# K210_Board.net
KiCad netlist of a schematic drawn in Altium Designer
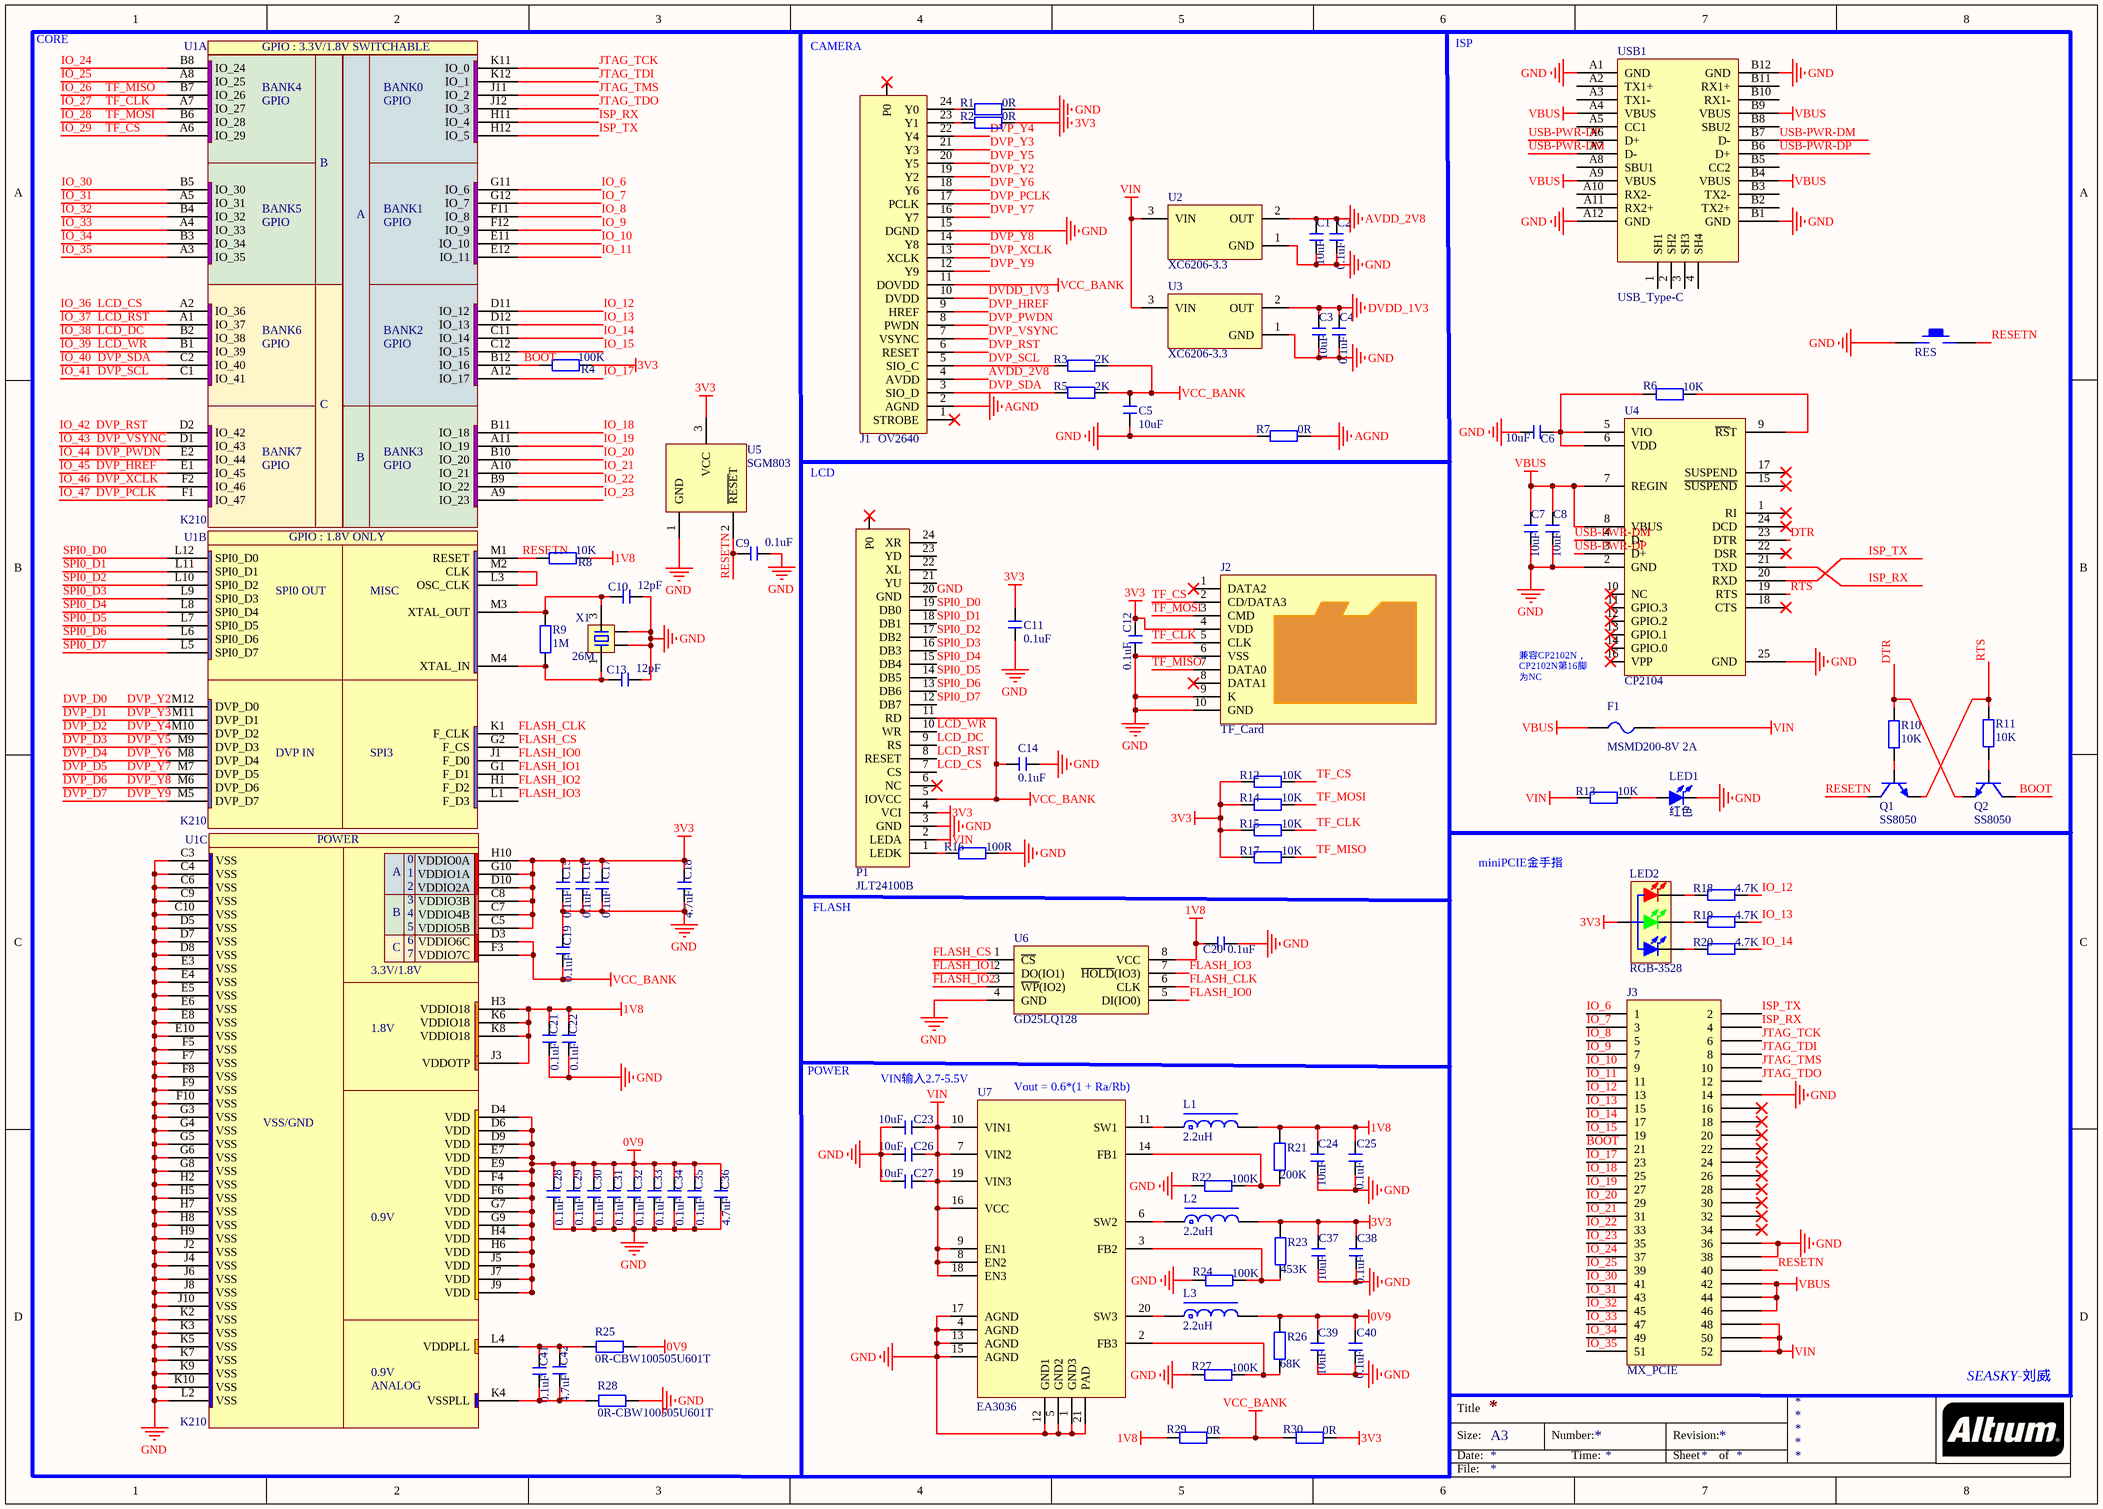
[diagram p0: K210_Board.SchDoc]

(export (version "E")
  (design (tool "Eeschema 10.0.6"))
  (components
    (comp (ref "C1")
      (value "10uF")
      (footprint "C 0402_M")
      (description "贴片电容")
      (libsource (lib "0.1 - 电阻-电容-电感") (part "C"))
    )
    (comp (ref "C2")
      (value "0.1uF")
      (footprint "C 0402_M")
      (description "贴片电容")
      (libsource (lib "0.1 - 电阻-电容-电感") (part "C"))
    )
    (comp (ref "C3")
      (value "10uF")
      (footprint "C 0402_M")
      (description "贴片电容")
      (libsource (lib "0.1 - 电阻-电容-电感") (part "C"))
    )
    (comp (ref "C4")
      (value "0.1uF")
      (footprint "C 0402_M")
      (description "贴片电容")
      (libsource (lib "0.1 - 电阻-电容-电感") (part "C"))
    )
    (comp (ref "C5")
      (value "10uF")
      (footprint "C 0402_M")
      (description "贴片电容")
      (libsource (lib "0.1 - 电阻-电容-电感") (part "C"))
    )
    (comp (ref "C6")
      (value "10uF")
      (footprint "C 0402_M")
      (description "贴片电容")
      (libsource (lib "0.1 - 电阻-电容-电感") (part "C"))
    )
    (comp (ref "C7")
      (value "10uF")
      (footprint "C 0402_M")
      (description "贴片电容")
      (libsource (lib "0.1 - 电阻-电容-电感") (part "C"))
    )
    (comp (ref "C8")
      (value "10uF")
      (footprint "C 0402_M")
      (description "贴片电容")
      (libsource (lib "0.1 - 电阻-电容-电感") (part "C"))
    )
    (comp (ref "C9")
      (value "0.1uF")
      (footprint "C 0402_M")
      (description "贴片电容")
      (libsource (lib "0.1 - 电阻-电容-电感") (part "C"))
    )
    (comp (ref "C10")
      (value "12pF")
      (footprint "C 0402_M")
      (description "贴片电容")
      (libsource (lib "0.1 - 电阻-电容-电感") (part "C"))
    )
    (comp (ref "C11")
      (value "0.1uF")
      (footprint "C 0402_M")
      (description "贴片电容")
      (libsource (lib "0.1 - 电阻-电容-电感") (part "C"))
    )
    (comp (ref "C12")
      (value "0.1uF")
      (footprint "C 0402_M")
      (description "贴片电容")
      (libsource (lib "0.1 - 电阻-电容-电感") (part "C"))
    )
    (comp (ref "C13")
      (value "12pF")
      (footprint "C 0402_M")
      (description "贴片电容")
      (libsource (lib "0.1 - 电阻-电容-电感") (part "C"))
    )
    (comp (ref "C14")
      (value "0.1uF")
      (footprint "C 0402_M")
      (description "贴片电容")
      (libsource (lib "0.1 - 电阻-电容-电感") (part "C"))
    )
    (comp (ref "C15")
      (value "0.1uF")
      (footprint "C 0402_M")
      (description "贴片电容")
      (libsource (lib "0.1 - 电阻-电容-电感") (part "C"))
    )
    (comp (ref "C16")
      (value "0.1uF")
      (footprint "C 0402_M")
      (description "贴片电容")
      (libsource (lib "0.1 - 电阻-电容-电感") (part "C"))
    )
    (comp (ref "C17")
      (value "0.1uF")
      (footprint "C 0402_M")
      (description "贴片电容")
      (libsource (lib "0.1 - 电阻-电容-电感") (part "C"))
    )
    (comp (ref "C18")
      (value "4.7uF")
      (footprint "C 0402_M")
      (description "贴片电容")
      (libsource (lib "0.1 - 电阻-电容-电感") (part "C"))
    )
    (comp (ref "C19")
      (value "0.1uF")
      (footprint "C 0402_M")
      (description "贴片电容")
      (libsource (lib "0.1 - 电阻-电容-电感") (part "C"))
    )
    (comp (ref "C20")
      (value "0.1uF")
      (footprint "C 0402_M")
      (description "贴片电容")
      (libsource (lib "0.1 - 电阻-电容-电感") (part "C"))
    )
    (comp (ref "C21")
      (value "0.1uF")
      (footprint "C 0402_M")
      (description "贴片电容")
      (libsource (lib "0.1 - 电阻-电容-电感") (part "C"))
    )
    (comp (ref "C22")
      (value "0.1uF")
      (footprint "C 0402_M")
      (description "贴片电容")
      (libsource (lib "0.1 - 电阻-电容-电感") (part "C"))
    )
    (comp (ref "C23")
      (value "10uF")
      (footprint "C 0402_M")
      (description "贴片电容")
      (libsource (lib "0.1 - 电阻-电容-电感") (part "C"))
    )
    (comp (ref "C24")
      (value "10uF")
      (footprint "C 0402_M")
      (description "贴片电容")
      (libsource (lib "0.1 - 电阻-电容-电感") (part "C"))
    )
    (comp (ref "C25")
      (value "0.1uF")
      (footprint "C 0402_M")
      (description "贴片电容")
      (libsource (lib "0.1 - 电阻-电容-电感") (part "C"))
    )
    (comp (ref "C26")
      (value "10uF")
      (footprint "C 0402_M")
      (description "贴片电容")
      (libsource (lib "0.1 - 电阻-电容-电感") (part "C"))
    )
    (comp (ref "C27")
      (value "10uF")
      (footprint "C 0402_M")
      (description "贴片电容")
      (libsource (lib "0.1 - 电阻-电容-电感") (part "C"))
    )
    (comp (ref "C28")
      (value "0.1uF")
      (footprint "C 0402_M")
      (description "贴片电容")
      (libsource (lib "0.1 - 电阻-电容-电感") (part "C"))
    )
    (comp (ref "C29")
      (value "0.1uF")
      (footprint "C 0402_M")
      (description "贴片电容")
      (libsource (lib "0.1 - 电阻-电容-电感") (part "C"))
    )
    (comp (ref "C30")
      (value "0.1uF")
      (footprint "C 0402_M")
      (description "贴片电容")
      (libsource (lib "0.1 - 电阻-电容-电感") (part "C"))
    )
    (comp (ref "C31")
      (value "0.1uF")
      (footprint "C 0402_M")
      (description "贴片电容")
      (libsource (lib "0.1 - 电阻-电容-电感") (part "C"))
    )
    (comp (ref "C32")
      (value "0.1uF")
      (footprint "C 0402_M")
      (description "贴片电容")
      (libsource (lib "0.1 - 电阻-电容-电感") (part "C"))
    )
    (comp (ref "C33")
      (value "0.1uF")
      (footprint "C 0402_M")
      (description "贴片电容")
      (libsource (lib "0.1 - 电阻-电容-电感") (part "C"))
    )
    (comp (ref "C34")
      (value "0.1uF")
      (footprint "C 0402_M")
      (description "贴片电容")
      (libsource (lib "0.1 - 电阻-电容-电感") (part "C"))
    )
    (comp (ref "C35")
      (value "0.1uF")
      (footprint "C 0402_M")
      (description "贴片电容")
      (libsource (lib "0.1 - 电阻-电容-电感") (part "C"))
    )
    (comp (ref "C36")
      (value "4.7uF")
      (footprint "C 0402_M")
      (description "贴片电容")
      (libsource (lib "0.1 - 电阻-电容-电感") (part "C"))
    )
    (comp (ref "C37")
      (value "10uF")
      (footprint "C 0402_M")
      (description "贴片电容")
      (libsource (lib "0.1 - 电阻-电容-电感") (part "C"))
    )
    (comp (ref "C38")
      (value "0.1uF")
      (footprint "C 0402_M")
      (description "贴片电容")
      (libsource (lib "0.1 - 电阻-电容-电感") (part "C"))
    )
    (comp (ref "C39")
      (value "10uF")
      (footprint "C 0402_M")
      (description "贴片电容")
      (libsource (lib "0.1 - 电阻-电容-电感") (part "C"))
    )
    (comp (ref "C40")
      (value "0.1uF")
      (footprint "C 0402_M")
      (description "贴片电容")
      (libsource (lib "0.1 - 电阻-电容-电感") (part "C"))
    )
    (comp (ref "C41")
      (value "0.1uF")
      (footprint "C 0402_M")
      (description "贴片电容")
      (libsource (lib "0.1 - 电阻-电容-电感") (part "C"))
    )
    (comp (ref "C42")
      (value "4.7uF")
      (footprint "C 0402_M")
      (description "贴片电容")
      (libsource (lib "0.1 - 电阻-电容-电感") (part "C"))
    )
    (comp (ref "F1")
      (value "MSMD200-8V 2A")
      (footprint "FU 1210")
      (description "贴片保险丝")
      (libsource (lib "2.0 - 保险丝-晶振-光耦") (part "FU"))
    )
    (comp (ref "J1")
      (value "OV2640")
      (footprint "FFC/SM0.5-2H24-OV5640")
      (description "Header, 24-Pin")
      (fields (field (name "PUBLISHER") "Altium Limited"))
      (libsource (lib "Vowstar_MCU") (part "OV5640"))
    )
    (comp (ref "J2")
      (value "TF_Card")
      (footprint "TF-SOCKET - short")
      (description "TF卡座")
      (libsource (lib "0.8 - 网口-音频插座") (part "TF_Card"))
    )
    (comp (ref "J3")
      (value "MX_PCIE")
      (footprint "miniPCIE")
      (description "mini-PCI-E")
      (libsource (lib "mx_pcb_library") (part "MX_PCIE"))
    )
    (comp (ref "L1")
      (value "2.2uH")
      (footprint "NR2520")
      (description "NR磁胶电感")
      (libsource (lib "0.1 - 电阻-电容-电感") (part "L-NR"))
    )
    (comp (ref "L2")
      (value "2.2uH")
      (footprint "NR2520")
      (description "NR磁胶电感")
      (libsource (lib "0.1 - 电阻-电容-电感") (part "L-NR"))
    )
    (comp (ref "L3")
      (value "2.2uH")
      (footprint "NR2520")
      (description "NR磁胶电感")
      (libsource (lib "0.1 - 电阻-电容-电感") (part "L-NR"))
    )
    (comp (ref "LED1")
      (value "红色")
      (footprint "LED 0805G")
      (description "贴片LED")
      (libsource (lib "0.3 - LED发光二极管") (part "LED-SMD"))
    )
    (comp (ref "LED2")
      (value "RGB-3528")
      (footprint "LED 3528-4Pin")
      (description "3528三基色LED")
      (libsource (lib "0.3 - LED发光二极管") (part "LED-RGB 3528"))
    )
    (comp (ref "P1")
      (value "JLT24100B")
      (footprint "FFC/SM0.5-2H24-LCD")
      (fields (field (name "PUBLISHER") "Altium Limited"))
      (libsource (lib "Schlib1") (part "JLT24100B"))
    )
    (comp (ref "Q1")
      (value "SS8050")
      (footprint "SOT23-3N")
      (description "高频放大-NPN型")
      (libsource (lib "0.4 - 三极管") (part "8050-SMD"))
    )
    (comp (ref "Q2")
      (value "SS8050")
      (footprint "SOT23-3N")
      (description "高频放大-NPN型")
      (libsource (lib "0.4 - 三极管") (part "8050-SMD"))
    )
    (comp (ref "R1")
      (value "0R")
      (footprint "R 0402_M")
      (description "贴片电阻")
      (libsource (lib "0.1 - 电阻-电容-电感") (part "R"))
    )
    (comp (ref "R2")
      (value "0R")
      (footprint "R 0402_M")
      (description "贴片电阻")
      (libsource (lib "0.1 - 电阻-电容-电感") (part "R"))
    )
    (comp (ref "R3")
      (value "2K")
      (footprint "R 0402_M")
      (description "贴片电阻")
      (libsource (lib "0.1 - 电阻-电容-电感") (part "R"))
    )
    (comp (ref "R4")
      (value "100K")
      (footprint "R 0402_M")
      (description "贴片电阻")
      (libsource (lib "0.1 - 电阻-电容-电感") (part "R"))
    )
    (comp (ref "R5")
      (value "2K")
      (footprint "R 0402_M")
      (description "贴片电阻")
      (libsource (lib "0.1 - 电阻-电容-电感") (part "R"))
    )
    (comp (ref "R6")
      (value "10K")
      (footprint "R 0402_M")
      (description "贴片电阻")
      (libsource (lib "0.1 - 电阻-电容-电感") (part "R"))
    )
    (comp (ref "R7")
      (value "0R")
      (footprint "R 0402_M")
      (description "贴片电阻")
      (libsource (lib "0.1 - 电阻-电容-电感") (part "R"))
    )
    (comp (ref "R8")
      (value "10K")
      (footprint "R 0402_M")
      (description "贴片电阻")
      (libsource (lib "0.1 - 电阻-电容-电感") (part "R"))
    )
    (comp (ref "R9")
      (value "1M")
      (footprint "R 0402_M")
      (description "贴片电阻")
      (libsource (lib "0.1 - 电阻-电容-电感") (part "R"))
    )
    (comp (ref "R10")
      (value "10K")
      (footprint "R 0402_M")
      (description "贴片电阻")
      (libsource (lib "0.1 - 电阻-电容-电感") (part "R"))
    )
    (comp (ref "R11")
      (value "10K")
      (footprint "R 0402_M")
      (description "贴片电阻")
      (libsource (lib "0.1 - 电阻-电容-电感") (part "R"))
    )
    (comp (ref "R12")
      (value "10K")
      (footprint "R 0402_M")
      (description "贴片电阻")
      (libsource (lib "0.1 - 电阻-电容-电感") (part "R"))
    )
    (comp (ref "R13")
      (value "10K")
      (footprint "R 0402_M")
      (description "贴片电阻")
      (libsource (lib "0.1 - 电阻-电容-电感") (part "R"))
    )
    (comp (ref "R14")
      (value "10K")
      (footprint "R 0402_M")
      (description "贴片电阻")
      (libsource (lib "0.1 - 电阻-电容-电感") (part "R"))
    )
    (comp (ref "R15")
      (value "10K")
      (footprint "R 0402_M")
      (description "贴片电阻")
      (libsource (lib "0.1 - 电阻-电容-电感") (part "R"))
    )
    (comp (ref "R16")
      (value "100R")
      (footprint "R 0402_M")
      (description "贴片电阻")
      (libsource (lib "0.1 - 电阻-电容-电感") (part "R"))
    )
    (comp (ref "R17")
      (value "10K")
      (footprint "R 0402_M")
      (description "贴片电阻")
      (libsource (lib "0.1 - 电阻-电容-电感") (part "R"))
    )
    (comp (ref "R18")
      (value "4.7K")
      (footprint "R 0402_M")
      (description "贴片电阻")
      (libsource (lib "0.1 - 电阻-电容-电感") (part "R"))
    )
    (comp (ref "R19")
      (value "4.7K")
      (footprint "R 0402_M")
      (description "贴片电阻")
      (libsource (lib "0.1 - 电阻-电容-电感") (part "R"))
    )
    (comp (ref "R20")
      (value "4.7K")
      (footprint "R 0402_M")
      (description "贴片电阻")
      (libsource (lib "0.1 - 电阻-电容-电感") (part "R"))
    )
    (comp (ref "R21")
      (value "200K")
      (footprint "R 0402_M")
      (description "贴片电阻")
      (libsource (lib "0.1 - 电阻-电容-电感") (part "R"))
    )
    (comp (ref "R22")
      (value "100K")
      (footprint "R 0402_M")
      (description "贴片电阻")
      (libsource (lib "0.1 - 电阻-电容-电感") (part "R"))
    )
    (comp (ref "R23")
      (value "453K")
      (footprint "R 0402_M")
      (description "贴片电阻")
      (libsource (lib "0.1 - 电阻-电容-电感") (part "R"))
    )
    (comp (ref "R24")
      (value "100K")
      (footprint "R 0402_M")
      (description "贴片电阻")
      (libsource (lib "0.1 - 电阻-电容-电感") (part "R"))
    )
    (comp (ref "R25")
      (value "0R-CBW100505U601T")
      (footprint "R 0402_M")
      (description "贴片电阻")
      (libsource (lib "0.1 - 电阻-电容-电感") (part "R"))
    )
    (comp (ref "R26")
      (value "68K")
      (footprint "R 0402_M")
      (description "贴片电阻")
      (libsource (lib "0.1 - 电阻-电容-电感") (part "R"))
    )
    (comp (ref "R27")
      (value "100K")
      (footprint "R 0402_M")
      (description "贴片电阻")
      (libsource (lib "0.1 - 电阻-电容-电感") (part "R"))
    )
    (comp (ref "R28")
      (value "0R-CBW100505U601T")
      (footprint "R 0402_M")
      (description "贴片电阻")
      (libsource (lib "0.1 - 电阻-电容-电感") (part "R"))
    )
    (comp (ref "R29")
      (value "0R")
      (footprint "R 0402_M")
      (description "贴片电阻")
      (libsource (lib "0.1 - 电阻-电容-电感") (part "R"))
    )
    (comp (ref "R30")
      (value "0R")
      (footprint "R 0402_M")
      (description "贴片电阻")
      (libsource (lib "0.1 - 电阻-电容-电感") (part "R"))
    )
    (comp (ref "RST1")
      (value "RES")
      (footprint "mx_pcb_library:SMD-3.2*4.2")
      (libsource (lib "mx_pcb_library") (part "KEY_M"))
    )
    (comp (ref "U1")
      (value "K210")
      (footprint "BGA144C65P12X12_800X800X95")
      (description "Canaan Kendryte K210 AI SoC")
      (libsource (lib "Vowstar_MCU") (part "K210"))
    )
    (comp (ref "U2")
      (value "XC6206-3.3")
      (footprint "2.07-SOT封装:SOT23-3N")
      (description "SOT-23,XC6206P332MR,MAX8V,100mA")
      (libsource (lib "1.1 - 电源类芯片") (part "XC6206-3.3"))
    )
    (comp (ref "U3")
      (value "XC6206-3.3")
      (footprint "2.07-SOT封装:SOT23-3N")
      (description "SOT-23,XC6206P332MR,MAX8V,100mA")
      (libsource (lib "1.1 - 电源类芯片") (part "XC6206-3.3"))
    )
    (comp (ref "U4")
      (value "CP2104")
      (footprint "QFN-24_L4.0-W4.0-P0.50-BL-EP2.8")
      (libsource (lib "Vowstar_MCU") (part "CP2104"))
    )
    (comp (ref "U5")
      (value "SGM803")
      (footprint "2.07-SOT封装:SOT23-3N")
      (libsource (lib "Vowstar_MCU") (part "SGM803"))
    )
    (comp (ref "U6")
      (value "GD25LQ128")
      (footprint "WSON-8_L8.0-W6.10-P1.27-BL-EP")
      (description "WSON-8")
      (libsource (lib "Vowstar_MCU") (part "GD25LQ128"))
    )
    (comp (ref "U7")
      (value "EA3036")
      (footprint "QFN20_40P300X300X80_HS-21N")
      (libsource (lib "Vowstar_MCU") (part "EA3036"))
    )
    (comp (ref "USB1")
      (value "USB_Type-C")
      (footprint "Type-C-TOP")
      (libsource (lib "Vowstar_MCU") (part "USB_Type-C"))
    )
    (comp (ref "X1")
      (value "26M")
      (footprint "OSC 3225-4P")
      (description "4脚无源晶振")
      (libsource (lib "2.0 - 保险丝-晶振-光耦") (part "XTAL-4P"))
    )
  )
  (nets
    (net (code "1") (name "/BOOT") (class "Default")
      (node (ref "J3") (pin "21") (pinfunction "21_21") (pintype "passive"))
      (node (ref "Q2") (pin "3") (pinfunction "C_3") (pintype "passive"))
      (node (ref "R4") (pin "1") (pinfunction "1_1") (pintype "passive"))
      (node (ref "U1") (pin "B12") (pinfunction "IO_16_B12") (pintype "passive"))
    )
    (net (code "2") (name "/DTR") (class "Default")
      (node (ref "Q2") (pin "2") (pinfunction "E_2") (pintype "passive"))
      (node (ref "R10") (pin "1") (pinfunction "1_1") (pintype "passive"))
      (node (ref "U4") (pin "23") (pinfunction "DTR_23") (pintype "passive"))
    )
    (net (code "3") (name "/DVP_D0") (class "Default")
      (node (ref "J1") (pin "19") (pinfunction "Y2_19") (pintype "passive"))
      (node (ref "U1") (pin "M12") (pinfunction "DVP_D0_M12") (pintype "passive"))
    )
    (net (code "4") (name "/DVP_D1") (class "Default")
      (node (ref "J1") (pin "21") (pinfunction "Y3_21") (pintype "passive"))
      (node (ref "U1") (pin "M11") (pinfunction "DVP_D1_M11") (pintype "passive"))
    )
    (net (code "5") (name "/DVP_D2") (class "Default")
      (node (ref "J1") (pin "22") (pinfunction "Y4_22") (pintype "passive"))
      (node (ref "U1") (pin "M10") (pinfunction "DVP_D2_M10") (pintype "passive"))
    )
    (net (code "6") (name "/DVP_D3") (class "Default")
      (node (ref "J1") (pin "20") (pinfunction "Y5_20") (pintype "passive"))
      (node (ref "U1") (pin "M9") (pinfunction "DVP_D3_M9") (pintype "passive"))
    )
    (net (code "7") (name "/DVP_D4") (class "Default")
      (node (ref "J1") (pin "18") (pinfunction "Y6_18") (pintype "passive"))
      (node (ref "U1") (pin "M8") (pinfunction "DVP_D4_M8") (pintype "passive"))
    )
    (net (code "8") (name "/DVP_D5") (class "Default")
      (node (ref "J1") (pin "16") (pinfunction "Y7_16") (pintype "passive"))
      (node (ref "U1") (pin "M7") (pinfunction "DVP_D5_M7") (pintype "passive"))
    )
    (net (code "9") (name "/DVP_D6") (class "Default")
      (node (ref "J1") (pin "14") (pinfunction "Y8_14") (pintype "passive"))
      (node (ref "U1") (pin "M6") (pinfunction "DVP_D6_M6") (pintype "passive"))
    )
    (net (code "10") (name "/DVP_D7") (class "Default")
      (node (ref "J1") (pin "12") (pinfunction "Y9_12") (pintype "passive"))
      (node (ref "U1") (pin "M5") (pinfunction "DVP_D7_M5") (pintype "passive"))
    )
    (net (code "11") (name "/DVP_HREF") (class "Default")
      (node (ref "J1") (pin "9") (pinfunction "HREF_9") (pintype "passive"))
      (node (ref "U1") (pin "E1") (pinfunction "IO_45_E1") (pintype "passive"))
    )
    (net (code "12") (name "/DVP_PCLK") (class "Default")
      (node (ref "J1") (pin "17") (pinfunction "PCLK_17") (pintype "passive"))
      (node (ref "U1") (pin "F1") (pinfunction "IO_47_F1") (pintype "passive"))
    )
    (net (code "13") (name "/DVP_PWDN") (class "Default")
      (node (ref "J1") (pin "8") (pinfunction "PWDN_8") (pintype "passive"))
      (node (ref "U1") (pin "E2") (pinfunction "IO_44_E2") (pintype "passive"))
    )
    (net (code "14") (name "/DVP_RST") (class "Default")
      (node (ref "J1") (pin "6") (pinfunction "RESET_6") (pintype "passive"))
      (node (ref "U1") (pin "D2") (pinfunction "IO_42_D2") (pintype "passive"))
    )
    (net (code "15") (name "/DVP_SCL") (class "Default")
      (node (ref "J1") (pin "5") (pinfunction "SIO_C_5") (pintype "passive"))
      (node (ref "R3") (pin "1") (pinfunction "1_1") (pintype "passive"))
      (node (ref "U1") (pin "C1") (pinfunction "IO_41_C1") (pintype "passive"))
    )
    (net (code "16") (name "/DVP_SDA") (class "Default")
      (node (ref "J1") (pin "3") (pinfunction "SIO_D_3") (pintype "passive"))
      (node (ref "R5") (pin "1") (pinfunction "1_1") (pintype "passive"))
      (node (ref "U1") (pin "C2") (pinfunction "IO_40_C2") (pintype "passive"))
    )
    (net (code "17") (name "/DVP_VSYNC") (class "Default")
      (node (ref "J1") (pin "7") (pinfunction "VSYNC_7") (pintype "passive"))
      (node (ref "U1") (pin "D1") (pinfunction "IO_43_D1") (pintype "passive"))
    )
    (net (code "18") (name "/DVP_XCLK") (class "Default")
      (node (ref "J1") (pin "13") (pinfunction "XCLK_13") (pintype "passive"))
      (node (ref "U1") (pin "F2") (pinfunction "IO_46_F2") (pintype "passive"))
    )
    (net (code "19") (name "/FLASH_CLK") (class "Default")
      (node (ref "U1") (pin "K1") (pinfunction "F_CLK_K1") (pintype "passive"))
      (node (ref "U6") (pin "6") (pinfunction "CLK_6") (pintype "passive"))
    )
    (net (code "20") (name "/FLASH_CS") (class "Default")
      (node (ref "U1") (pin "G2") (pinfunction "F_CS_G2") (pintype "passive"))
      (node (ref "U6") (pin "1") (pinfunction "~{CS}_1") (pintype "passive"))
    )
    (net (code "21") (name "/FLASH_IO0") (class "Default")
      (node (ref "U1") (pin "J1") (pinfunction "F_D0_J1") (pintype "passive"))
      (node (ref "U6") (pin "5") (pinfunction "DI(IO0)_5") (pintype "passive"))
    )
    (net (code "22") (name "/FLASH_IO1") (class "Default")
      (node (ref "U1") (pin "G1") (pinfunction "F_D1_G1") (pintype "passive"))
      (node (ref "U6") (pin "2") (pinfunction "DO(IO1)_2") (pintype "passive"))
    )
    (net (code "23") (name "/FLASH_IO2") (class "Default")
      (node (ref "U1") (pin "H1") (pinfunction "F_D2_H1") (pintype "passive"))
      (node (ref "U6") (pin "3") (pinfunction "~{WP}(IO2)_3") (pintype "passive"))
    )
    (net (code "24") (name "/FLASH_IO3") (class "Default")
      (node (ref "U1") (pin "L1") (pinfunction "F_D3_L1") (pintype "passive"))
      (node (ref "U6") (pin "7") (pinfunction "~{HOLD}(IO3)_7") (pintype "passive"))
    )
    (net (code "25") (name "/IO_6") (class "Default")
      (node (ref "J3") (pin "1") (pinfunction "1_1") (pintype "passive"))
      (node (ref "U1") (pin "G11") (pinfunction "IO_6_G11") (pintype "passive"))
    )
    (net (code "26") (name "/IO_7") (class "Default")
      (node (ref "J3") (pin "3") (pinfunction "3_3") (pintype "passive"))
      (node (ref "U1") (pin "G12") (pinfunction "IO_7_G12") (pintype "passive"))
    )
    (net (code "27") (name "/IO_8") (class "Default")
      (node (ref "J3") (pin "5") (pinfunction "5_5") (pintype "passive"))
      (node (ref "U1") (pin "F11") (pinfunction "IO_8_F11") (pintype "passive"))
    )
    (net (code "28") (name "/IO_9") (class "Default")
      (node (ref "J3") (pin "7") (pinfunction "7_7") (pintype "passive"))
      (node (ref "U1") (pin "F12") (pinfunction "IO_9_F12") (pintype "passive"))
    )
    (net (code "29") (name "/IO_10") (class "Default")
      (node (ref "J3") (pin "9") (pinfunction "9_9") (pintype "passive"))
      (node (ref "U1") (pin "E11") (pinfunction "IO_10_E11") (pintype "passive"))
    )
    (net (code "30") (name "/IO_11") (class "Default")
      (node (ref "J3") (pin "11") (pinfunction "11_11") (pintype "passive"))
      (node (ref "U1") (pin "E12") (pinfunction "IO_11_E12") (pintype "passive"))
    )
    (net (code "31") (name "/IO_12") (class "Default")
      (node (ref "J3") (pin "13") (pinfunction "13_13") (pintype "passive"))
      (node (ref "R18") (pin "2") (pinfunction "2_2") (pintype "passive"))
      (node (ref "U1") (pin "D11") (pinfunction "IO_12_D11") (pintype "passive"))
    )
    (net (code "32") (name "/IO_13") (class "Default")
      (node (ref "J3") (pin "15") (pinfunction "15_15") (pintype "passive"))
      (node (ref "R19") (pin "2") (pinfunction "2_2") (pintype "passive"))
      (node (ref "U1") (pin "D12") (pinfunction "IO_13_D12") (pintype "passive"))
    )
    (net (code "33") (name "/IO_14") (class "Default")
      (node (ref "J3") (pin "17") (pinfunction "17_17") (pintype "passive"))
      (node (ref "R20") (pin "2") (pinfunction "2_2") (pintype "passive"))
      (node (ref "U1") (pin "C11") (pinfunction "IO_14_C11") (pintype "passive"))
    )
    (net (code "34") (name "/IO_15") (class "Default")
      (node (ref "J3") (pin "19") (pinfunction "19_19") (pintype "passive"))
      (node (ref "U1") (pin "C12") (pinfunction "IO_15_C12") (pintype "passive"))
    )
    (net (code "35") (name "/IO_17") (class "Default")
      (node (ref "J3") (pin "23") (pinfunction "23_23") (pintype "passive"))
      (node (ref "U1") (pin "A12") (pinfunction "IO_17_A12") (pintype "passive"))
    )
    (net (code "36") (name "/IO_18") (class "Default")
      (node (ref "J3") (pin "25") (pinfunction "25_25") (pintype "passive"))
      (node (ref "U1") (pin "B11") (pinfunction "IO_18_B11") (pintype "passive"))
    )
    (net (code "37") (name "/IO_19") (class "Default")
      (node (ref "J3") (pin "27") (pinfunction "27_27") (pintype "passive"))
      (node (ref "U1") (pin "A11") (pinfunction "IO_19_A11") (pintype "passive"))
    )
    (net (code "38") (name "/IO_20") (class "Default")
      (node (ref "J3") (pin "29") (pinfunction "29_29") (pintype "passive"))
      (node (ref "U1") (pin "B10") (pinfunction "IO_20_B10") (pintype "passive"))
    )
    (net (code "39") (name "/IO_21") (class "Default")
      (node (ref "J3") (pin "31") (pinfunction "31_31") (pintype "passive"))
      (node (ref "U1") (pin "A10") (pinfunction "IO_21_A10") (pintype "passive"))
    )
    (net (code "40") (name "/IO_22") (class "Default")
      (node (ref "J3") (pin "33") (pinfunction "33_33") (pintype "passive"))
      (node (ref "U1") (pin "B9") (pinfunction "IO_22_B9") (pintype "passive"))
    )
    (net (code "41") (name "/IO_23") (class "Default")
      (node (ref "J3") (pin "35") (pinfunction "35_35") (pintype "passive"))
      (node (ref "U1") (pin "A9") (pinfunction "IO_23_A9") (pintype "passive"))
    )
    (net (code "42") (name "/IO_24") (class "Default")
      (node (ref "J3") (pin "37") (pinfunction "37_37") (pintype "passive"))
      (node (ref "U1") (pin "B8") (pinfunction "IO_24_B8") (pintype "passive"))
    )
    (net (code "43") (name "/IO_25") (class "Default")
      (node (ref "J3") (pin "39") (pinfunction "39_39") (pintype "passive"))
      (node (ref "U1") (pin "A8") (pinfunction "IO_25_A8") (pintype "passive"))
    )
    (net (code "44") (name "/IO_26") (class "Default")
      (node (ref "J2") (pin "7") (pinfunction "DATA0_7") (pintype "passive"))
      (node (ref "R17") (pin "2") (pinfunction "2_2") (pintype "passive"))
      (node (ref "U1") (pin "B7") (pinfunction "IO_26_B7") (pintype "passive"))
    )
    (net (code "45") (name "/IO_27") (class "Default")
      (node (ref "J2") (pin "5") (pinfunction "CLK_5") (pintype "passive"))
      (node (ref "R15") (pin "2") (pinfunction "2_2") (pintype "passive"))
      (node (ref "U1") (pin "A7") (pinfunction "IO_27_A7") (pintype "passive"))
    )
    (net (code "46") (name "/IO_28") (class "Default")
      (node (ref "J2") (pin "3") (pinfunction "CMD_3") (pintype "passive"))
      (node (ref "R14") (pin "2") (pinfunction "2_2") (pintype "passive"))
      (node (ref "U1") (pin "B6") (pinfunction "IO_28_B6") (pintype "passive"))
    )
    (net (code "47") (name "/IO_29") (class "Default")
      (node (ref "J2") (pin "2") (pinfunction "CD/DATA3_2") (pintype "passive"))
      (node (ref "R12") (pin "2") (pinfunction "2_2") (pintype "passive"))
      (node (ref "U1") (pin "A6") (pinfunction "IO_29_A6") (pintype "passive"))
    )
    (net (code "48") (name "/IO_30") (class "Default")
      (node (ref "J3") (pin "41") (pinfunction "41_41") (pintype "passive"))
      (node (ref "U1") (pin "B5") (pinfunction "IO_30_B5") (pintype "passive"))
    )
    (net (code "49") (name "/IO_31") (class "Default")
      (node (ref "J3") (pin "43") (pinfunction "43_43") (pintype "passive"))
      (node (ref "U1") (pin "A5") (pinfunction "IO_31_A5") (pintype "passive"))
    )
    (net (code "50") (name "/IO_32") (class "Default")
      (node (ref "J3") (pin "45") (pinfunction "45_45") (pintype "passive"))
      (node (ref "U1") (pin "B4") (pinfunction "IO_32_B4") (pintype "passive"))
    )
    (net (code "51") (name "/IO_33") (class "Default")
      (node (ref "J3") (pin "47") (pinfunction "47_47") (pintype "passive"))
      (node (ref "U1") (pin "A4") (pinfunction "IO_33_A4") (pintype "passive"))
    )
    (net (code "52") (name "/IO_34") (class "Default")
      (node (ref "J3") (pin "49") (pinfunction "49_49") (pintype "passive"))
      (node (ref "U1") (pin "B3") (pinfunction "IO_34_B3") (pintype "passive"))
    )
    (net (code "53") (name "/IO_35") (class "Default")
      (node (ref "J3") (pin "51") (pinfunction "51_51") (pintype "passive"))
      (node (ref "U1") (pin "A3") (pinfunction "IO_35_A3") (pintype "passive"))
    )
    (net (code "54") (name "/IO_36") (class "Default")
      (node (ref "P1") (pin "7") (pinfunction "CS_7") (pintype "passive"))
      (node (ref "U1") (pin "A2") (pinfunction "IO_36_A2") (pintype "passive"))
    )
    (net (code "55") (name "/IO_37") (class "Default")
      (node (ref "P1") (pin "8") (pinfunction "RESET_8") (pintype "passive"))
      (node (ref "U1") (pin "A1") (pinfunction "IO_37_A1") (pintype "passive"))
    )
    (net (code "56") (name "/IO_38") (class "Default")
      (node (ref "P1") (pin "9") (pinfunction "RS_9") (pintype "passive"))
      (node (ref "U1") (pin "B2") (pinfunction "IO_38_B2") (pintype "passive"))
    )
    (net (code "57") (name "/IO_39") (class "Default")
      (node (ref "P1") (pin "10") (pinfunction "WR_10") (pintype "passive"))
      (node (ref "U1") (pin "B1") (pinfunction "IO_39_B1") (pintype "passive"))
    )
    (net (code "58") (name "/ISP_RX") (class "Default")
      (node (ref "J3") (pin "4") (pinfunction "4_4") (pintype "passive"))
      (node (ref "U1") (pin "H11") (pinfunction "IO_4_H11") (pintype "passive"))
      (node (ref "U4") (pin "21") (pinfunction "TXD_21") (pintype "passive"))
    )
    (net (code "59") (name "/ISP_TX") (class "Default")
      (node (ref "J3") (pin "2") (pinfunction "2_2") (pintype "passive"))
      (node (ref "U1") (pin "H12") (pinfunction "IO_5_H12") (pintype "passive"))
      (node (ref "U4") (pin "20") (pinfunction "RXD_20") (pintype "passive"))
    )
    (net (code "60") (name "/JTAG_TCK") (class "Default")
      (node (ref "J3") (pin "6") (pinfunction "6_6") (pintype "passive"))
      (node (ref "U1") (pin "K11") (pinfunction "IO_0_K11") (pintype "passive"))
    )
    (net (code "61") (name "/JTAG_TDI") (class "Default")
      (node (ref "J3") (pin "8") (pinfunction "8_8") (pintype "passive"))
      (node (ref "U1") (pin "K12") (pinfunction "IO_1_K12") (pintype "passive"))
    )
    (net (code "62") (name "/JTAG_TDO") (class "Default")
      (node (ref "J3") (pin "12") (pinfunction "12_12") (pintype "passive"))
      (node (ref "U1") (pin "J12") (pinfunction "IO_3_J12") (pintype "passive"))
    )
    (net (code "63") (name "/JTAG_TMS") (class "Default")
      (node (ref "J3") (pin "10") (pinfunction "10_10") (pintype "passive"))
      (node (ref "U1") (pin "J11") (pinfunction "IO_2_J11") (pintype "passive"))
    )
    (net (code "64") (name "/RESETN") (class "Default")
      (node (ref "C9") (pin "1") (pinfunction "1_1") (pintype "passive"))
      (node (ref "J3") (pin "40") (pinfunction "40_40") (pintype "passive"))
      (node (ref "Q1") (pin "3") (pinfunction "C_3") (pintype "passive"))
      (node (ref "R8") (pin "1") (pinfunction "1_1") (pintype "passive"))
      (node (ref "RST1") (pin "2") (pinfunction "2_2") (pintype "passive"))
      (node (ref "U1") (pin "M1") (pinfunction "RESET_M1") (pintype "passive"))
      (node (ref "U5") (pin "2") (pinfunction "~{RESE}T_2") (pintype "passive"))
    )
    (net (code "65") (name "/RTS") (class "Default")
      (node (ref "Q1") (pin "2") (pinfunction "E_2") (pintype "passive"))
      (node (ref "R11") (pin "1") (pinfunction "1_1") (pintype "passive"))
      (node (ref "U4") (pin "19") (pinfunction "RTS_19") (pintype "passive"))
    )
    (net (code "66") (name "/SPI0_D0") (class "Default")
      (node (ref "P1") (pin "19") (pinfunction "DB0_19") (pintype "passive"))
      (node (ref "U1") (pin "L12") (pinfunction "SPI0_D0_L12") (pintype "passive"))
    )
    (net (code "67") (name "/SPI0_D1") (class "Default")
      (node (ref "P1") (pin "18") (pinfunction "DB1_18") (pintype "passive"))
      (node (ref "U1") (pin "L11") (pinfunction "SPI0_D1_L11") (pintype "passive"))
    )
    (net (code "68") (name "/SPI0_D2") (class "Default")
      (node (ref "P1") (pin "17") (pinfunction "DB2_17") (pintype "passive"))
      (node (ref "U1") (pin "L10") (pinfunction "SPI0_D2_L10") (pintype "passive"))
    )
    (net (code "69") (name "/SPI0_D3") (class "Default")
      (node (ref "P1") (pin "16") (pinfunction "DB3_16") (pintype "passive"))
      (node (ref "U1") (pin "L9") (pinfunction "SPI0_D3_L9") (pintype "passive"))
    )
    (net (code "70") (name "/SPI0_D4") (class "Default")
      (node (ref "P1") (pin "15") (pinfunction "DB4_15") (pintype "passive"))
      (node (ref "U1") (pin "L8") (pinfunction "SPI0_D4_L8") (pintype "passive"))
    )
    (net (code "71") (name "/SPI0_D5") (class "Default")
      (node (ref "P1") (pin "14") (pinfunction "DB5_14") (pintype "passive"))
      (node (ref "U1") (pin "L7") (pinfunction "SPI0_D5_L7") (pintype "passive"))
    )
    (net (code "72") (name "/SPI0_D6") (class "Default")
      (node (ref "P1") (pin "13") (pinfunction "DB6_13") (pintype "passive"))
      (node (ref "U1") (pin "L6") (pinfunction "SPI0_D6_L6") (pintype "passive"))
    )
    (net (code "73") (name "/SPI0_D7") (class "Default")
      (node (ref "P1") (pin "12") (pinfunction "DB7_12") (pintype "passive"))
      (node (ref "U1") (pin "L5") (pinfunction "SPI0_D7_L5") (pintype "passive"))
    )
    (net (code "74") (name "/USB-PWR-DM") (class "Default")
      (node (ref "U4") (pin "4") (pinfunction "D-_4") (pintype "passive"))
      (node (ref "USB1") (pin "A7") (pinfunction "D-_A7") (pintype "passive"))
      (node (ref "USB1") (pin "B7") (pinfunction "D-_B7") (pintype "passive"))
    )
    (net (code "75") (name "/USB-PWR-DP") (class "Default")
      (node (ref "U4") (pin "3") (pinfunction "D+_3") (pintype "passive"))
      (node (ref "USB1") (pin "A6") (pinfunction "D+_A6") (pintype "passive"))
      (node (ref "USB1") (pin "B6") (pinfunction "D+_B6") (pintype "passive"))
    )
    (net (code "76") (name "0V9") (class "Default")
      (node (ref "C28") (pin "1") (pinfunction "1_1") (pintype "passive"))
      (node (ref "C29") (pin "1") (pinfunction "1_1") (pintype "passive"))
      (node (ref "C30") (pin "1") (pinfunction "1_1") (pintype "passive"))
      (node (ref "C31") (pin "1") (pinfunction "1_1") (pintype "passive"))
      (node (ref "C32") (pin "1") (pinfunction "1_1") (pintype "passive"))
      (node (ref "C33") (pin "1") (pinfunction "1_1") (pintype "passive"))
      (node (ref "C34") (pin "1") (pinfunction "1_1") (pintype "passive"))
      (node (ref "C35") (pin "1") (pinfunction "1_1") (pintype "passive"))
      (node (ref "C36") (pin "1") (pinfunction "1_1") (pintype "passive"))
      (node (ref "C39") (pin "2") (pinfunction "2_2") (pintype "passive"))
      (node (ref "C40") (pin "2") (pinfunction "2_2") (pintype "passive"))
      (node (ref "L3") (pin "2") (pinfunction "2_2") (pintype "passive"))
      (node (ref "R25") (pin "2") (pinfunction "2_2") (pintype "passive"))
      (node (ref "R26") (pin "2") (pinfunction "2_2") (pintype "passive"))
      (node (ref "U1") (pin "D4") (pinfunction "VDD_D4") (pintype "power_in"))
      (node (ref "U1") (pin "D6") (pinfunction "VDD_D6") (pintype "power_in"))
      (node (ref "U1") (pin "D9") (pinfunction "VDD_D9") (pintype "power_in"))
      (node (ref "U1") (pin "E7") (pinfunction "VDD_E7") (pintype "power_in"))
      (node (ref "U1") (pin "E9") (pinfunction "VDD_E9") (pintype "power_in"))
      (node (ref "U1") (pin "F4") (pinfunction "VDD_F4") (pintype "power_in"))
      (node (ref "U1") (pin "F6") (pinfunction "VDD_F6") (pintype "power_in"))
      (node (ref "U1") (pin "G7") (pinfunction "VDD_G7") (pintype "power_in"))
      (node (ref "U1") (pin "G9") (pinfunction "VDD_G9") (pintype "power_in"))
      (node (ref "U1") (pin "H4") (pinfunction "VDD_H4") (pintype "power_in"))
      (node (ref "U1") (pin "H6") (pinfunction "VDD_H6") (pintype "power_in"))
      (node (ref "U1") (pin "J5") (pinfunction "VDD_J5") (pintype "power_in"))
      (node (ref "U1") (pin "J7") (pinfunction "VDD_J7") (pintype "power_in"))
      (node (ref "U1") (pin "J9") (pinfunction "VDD_J9") (pintype "power_in"))
    )
    (net (code "77") (name "1V8") (class "Default")
      (node (ref "C20") (pin "2") (pinfunction "2_2") (pintype "passive"))
      (node (ref "C21") (pin "1") (pinfunction "1_1") (pintype "passive"))
      (node (ref "C22") (pin "1") (pinfunction "1_1") (pintype "passive"))
      (node (ref "C24") (pin "2") (pinfunction "2_2") (pintype "passive"))
      (node (ref "C25") (pin "2") (pinfunction "2_2") (pintype "passive"))
      (node (ref "L1") (pin "2") (pinfunction "2_2") (pintype "passive"))
      (node (ref "R21") (pin "2") (pinfunction "2_2") (pintype "passive"))
      (node (ref "R29") (pin "2") (pinfunction "2_2") (pintype "passive"))
      (node (ref "R8") (pin "2") (pinfunction "2_2") (pintype "passive"))
      (node (ref "U1") (pin "H3") (pinfunction "VDDIO18_H3") (pintype "power_in"))
      (node (ref "U1") (pin "J3") (pinfunction "VDDOTP_J3") (pintype "power_in"))
      (node (ref "U1") (pin "K6") (pinfunction "VDDIO18_K6") (pintype "power_in"))
      (node (ref "U1") (pin "K8") (pinfunction "VDDIO18_K8") (pintype "power_in"))
      (node (ref "U6") (pin "8") (pinfunction "VCC_8") (pintype "passive"))
    )
    (net (code "78") (name "3V3") (class "Default")
      (node (ref "C11") (pin "1") (pinfunction "1_1") (pintype "passive"))
      (node (ref "C12") (pin "1") (pinfunction "1_1") (pintype "passive"))
      (node (ref "C15") (pin "2") (pinfunction "2_2") (pintype "passive"))
      (node (ref "C16") (pin "2") (pinfunction "2_2") (pintype "passive"))
      (node (ref "C17") (pin "2") (pinfunction "2_2") (pintype "passive"))
      (node (ref "C18") (pin "2") (pinfunction "2_2") (pintype "passive"))
      (node (ref "C37") (pin "2") (pinfunction "2_2") (pintype "passive"))
      (node (ref "C38") (pin "2") (pinfunction "2_2") (pintype "passive"))
      (node (ref "J2") (pin "4") (pinfunction "VDD_4") (pintype "passive"))
      (node (ref "L2") (pin "2") (pinfunction "2_2") (pintype "passive"))
      (node (ref "LED2") (pin "4") (pinfunction "A_4") (pintype "passive"))
      (node (ref "P1") (pin "4") (pinfunction "VCI_4") (pintype "passive"))
      (node (ref "R12") (pin "1") (pinfunction "1_1") (pintype "passive"))
      (node (ref "R14") (pin "1") (pinfunction "1_1") (pintype "passive"))
      (node (ref "R15") (pin "1") (pinfunction "1_1") (pintype "passive"))
      (node (ref "R17") (pin "1") (pinfunction "1_1") (pintype "passive"))
      (node (ref "R2") (pin "2") (pinfunction "2_2") (pintype "passive"))
      (node (ref "R23") (pin "2") (pinfunction "2_2") (pintype "passive"))
      (node (ref "R30") (pin "1") (pinfunction "1_1") (pintype "passive"))
      (node (ref "R4") (pin "2") (pinfunction "2_2") (pintype "passive"))
      (node (ref "U1") (pin "C5") (pinfunction "VDDIO5B_C5") (pintype "power_in"))
      (node (ref "U1") (pin "C7") (pinfunction "VDDIO4B_C7") (pintype "power_in"))
      (node (ref "U1") (pin "C8") (pinfunction "VDDIO3B_C8") (pintype "power_in"))
      (node (ref "U1") (pin "D10") (pinfunction "VDDIO2A_D10") (pintype "power_in"))
      (node (ref "U1") (pin "G10") (pinfunction "VDDIO1A_G10") (pintype "power_in"))
      (node (ref "U1") (pin "H10") (pinfunction "VDDIO0A_H10") (pintype "power_in"))
      (node (ref "U5") (pin "3") (pinfunction "VCC_3") (pintype "passive"))
    )
    (net (code "79") (name "AGND") (class "Default")
      (node (ref "J1") (pin "2") (pinfunction "AGND_2") (pintype "passive"))
      (node (ref "R7") (pin "2") (pinfunction "2_2") (pintype "passive"))
    )
    (net (code "80") (name "AVDD_2V8") (class "Default")
      (node (ref "C1") (pin "2") (pinfunction "2_2") (pintype "passive"))
      (node (ref "C2") (pin "2") (pinfunction "2_2") (pintype "passive"))
      (node (ref "J1") (pin "4") (pinfunction "AVDD_4") (pintype "passive"))
      (node (ref "U2") (pin "2") (pinfunction "OUT_2") (pintype "passive"))
    )
    (net (code "81") (name "DVDD_1V3") (class "Default")
      (node (ref "C3") (pin "2") (pinfunction "2_2") (pintype "passive"))
      (node (ref "C4") (pin "2") (pinfunction "2_2") (pintype "passive"))
      (node (ref "J1") (pin "10") (pinfunction "DVDD_10") (pintype "passive"))
      (node (ref "U3") (pin "2") (pinfunction "OUT_2") (pintype "passive"))
    )
    (net (code "82") (name "GND") (class "Default")
      (node (ref "C1") (pin "1") (pinfunction "1_1") (pintype "passive"))
      (node (ref "C10") (pin "2") (pinfunction "2_2") (pintype "passive"))
      (node (ref "C11") (pin "2") (pinfunction "2_2") (pintype "passive"))
      (node (ref "C12") (pin "2") (pinfunction "2_2") (pintype "passive"))
      (node (ref "C13") (pin "2") (pinfunction "2_2") (pintype "passive"))
      (node (ref "C14") (pin "1") (pinfunction "1_1") (pintype "passive"))
      (node (ref "C15") (pin "1") (pinfunction "1_1") (pintype "passive"))
      (node (ref "C16") (pin "1") (pinfunction "1_1") (pintype "passive"))
      (node (ref "C17") (pin "1") (pinfunction "1_1") (pintype "passive"))
      (node (ref "C18") (pin "1") (pinfunction "1_1") (pintype "passive"))
      (node (ref "C19") (pin "1") (pinfunction "1_1") (pintype "passive"))
      (node (ref "C2") (pin "1") (pinfunction "1_1") (pintype "passive"))
      (node (ref "C20") (pin "1") (pinfunction "1_1") (pintype "passive"))
      (node (ref "C21") (pin "2") (pinfunction "2_2") (pintype "passive"))
      (node (ref "C22") (pin "2") (pinfunction "2_2") (pintype "passive"))
      (node (ref "C23") (pin "2") (pinfunction "2_2") (pintype "passive"))
      (node (ref "C24") (pin "1") (pinfunction "1_1") (pintype "passive"))
      (node (ref "C25") (pin "1") (pinfunction "1_1") (pintype "passive"))
      (node (ref "C26") (pin "2") (pinfunction "2_2") (pintype "passive"))
      (node (ref "C27") (pin "2") (pinfunction "2_2") (pintype "passive"))
      (node (ref "C28") (pin "2") (pinfunction "2_2") (pintype "passive"))
      (node (ref "C29") (pin "2") (pinfunction "2_2") (pintype "passive"))
      (node (ref "C3") (pin "1") (pinfunction "1_1") (pintype "passive"))
      (node (ref "C30") (pin "2") (pinfunction "2_2") (pintype "passive"))
      (node (ref "C31") (pin "2") (pinfunction "2_2") (pintype "passive"))
      (node (ref "C32") (pin "2") (pinfunction "2_2") (pintype "passive"))
      (node (ref "C33") (pin "2") (pinfunction "2_2") (pintype "passive"))
      (node (ref "C34") (pin "2") (pinfunction "2_2") (pintype "passive"))
      (node (ref "C35") (pin "2") (pinfunction "2_2") (pintype "passive"))
      (node (ref "C36") (pin "2") (pinfunction "2_2") (pintype "passive"))
      (node (ref "C37") (pin "1") (pinfunction "1_1") (pintype "passive"))
      (node (ref "C38") (pin "1") (pinfunction "1_1") (pintype "passive"))
      (node (ref "C39") (pin "1") (pinfunction "1_1") (pintype "passive"))
      (node (ref "C4") (pin "1") (pinfunction "1_1") (pintype "passive"))
      (node (ref "C40") (pin "1") (pinfunction "1_1") (pintype "passive"))
      (node (ref "C5") (pin "2") (pinfunction "2_2") (pintype "passive"))
      (node (ref "C6") (pin "2") (pinfunction "2_2") (pintype "passive"))
      (node (ref "C7") (pin "1") (pinfunction "1_1") (pintype "passive"))
      (node (ref "C8") (pin "1") (pinfunction "1_1") (pintype "passive"))
      (node (ref "C9") (pin "2") (pinfunction "2_2") (pintype "passive"))
      (node (ref "J1") (pin "15") (pinfunction "DGND_15") (pintype "passive"))
      (node (ref "J2") (pin "10") (pinfunction "GND_10") (pintype "passive"))
      (node (ref "J2") (pin "6") (pinfunction "VSS_6") (pintype "passive"))
      (node (ref "J2") (pin "9") (pinfunction "K_9") (pintype "passive"))
      (node (ref "J3") (pin "14") (pinfunction "14_14") (pintype "passive"))
      (node (ref "J3") (pin "36") (pinfunction "36_36") (pintype "passive"))
      (node (ref "J3") (pin "38") (pinfunction "38_38") (pintype "passive"))
      (node (ref "LED1") (pin "2") (pinfunction "K_2") (pintype "passive"))
      (node (ref "P1") (pin "20") (pinfunction "GND_20") (pintype "passive"))
      (node (ref "P1") (pin "3") (pinfunction "GND_3") (pintype "passive"))
      (node (ref "R1") (pin "2") (pinfunction "2_2") (pintype "passive"))
      (node (ref "R16") (pin "2") (pinfunction "2_2") (pintype "passive"))
      (node (ref "R22") (pin "2") (pinfunction "2_2") (pintype "passive"))
      (node (ref "R24") (pin "2") (pinfunction "2_2") (pintype "passive"))
      (node (ref "R27") (pin "2") (pinfunction "2_2") (pintype "passive"))
      (node (ref "R28") (pin "2") (pinfunction "2_2") (pintype "passive"))
      (node (ref "R7") (pin "1") (pinfunction "1_1") (pintype "passive"))
      (node (ref "RST1") (pin "1") (pinfunction "1_1") (pintype "passive"))
      (node (ref "U1") (pin "C10") (pinfunction "VSS_C10") (pintype "power_in"))
      (node (ref "U1") (pin "C3") (pinfunction "VSS_C3") (pintype "power_in"))
      (node (ref "U1") (pin "C4") (pinfunction "VSS_C4") (pintype "power_in"))
      (node (ref "U1") (pin "C6") (pinfunction "VSS_C6") (pintype "power_in"))
      (node (ref "U1") (pin "C9") (pinfunction "VSS_C9") (pintype "power_in"))
      (node (ref "U1") (pin "D5") (pinfunction "VSS_D5") (pintype "power_in"))
      (node (ref "U1") (pin "D7") (pinfunction "VSS_D7") (pintype "power_in"))
      (node (ref "U1") (pin "D8") (pinfunction "VSS_D8") (pintype "power_in"))
      (node (ref "U1") (pin "E10") (pinfunction "VSS_E10") (pintype "power_in"))
      (node (ref "U1") (pin "E3") (pinfunction "VSS_E3") (pintype "power_in"))
      (node (ref "U1") (pin "E4") (pinfunction "VSS_E4") (pintype "power_in"))
      (node (ref "U1") (pin "E5") (pinfunction "VSS_E5") (pintype "power_in"))
      (node (ref "U1") (pin "E6") (pinfunction "VSS_E6") (pintype "power_in"))
      (node (ref "U1") (pin "E8") (pinfunction "VSS_E8") (pintype "power_in"))
      (node (ref "U1") (pin "F10") (pinfunction "VSS_F10") (pintype "power_in"))
      (node (ref "U1") (pin "F5") (pinfunction "VSS_F5") (pintype "power_in"))
      (node (ref "U1") (pin "F7") (pinfunction "VSS_F7") (pintype "power_in"))
      (node (ref "U1") (pin "F8") (pinfunction "VSS_F8") (pintype "power_in"))
      (node (ref "U1") (pin "F9") (pinfunction "VSS_F9") (pintype "power_in"))
      (node (ref "U1") (pin "G3") (pinfunction "VSS_G3") (pintype "power_in"))
      (node (ref "U1") (pin "G4") (pinfunction "VSS_G4") (pintype "power_in"))
      (node (ref "U1") (pin "G5") (pinfunction "VSS_G5") (pintype "power_in"))
      (node (ref "U1") (pin "G6") (pinfunction "VSS_G6") (pintype "power_in"))
      (node (ref "U1") (pin "G8") (pinfunction "VSS_G8") (pintype "power_in"))
      (node (ref "U1") (pin "H2") (pinfunction "VSS_H2") (pintype "power_in"))
      (node (ref "U1") (pin "H5") (pinfunction "VSS_H5") (pintype "power_in"))
      (node (ref "U1") (pin "H7") (pinfunction "VSS_H7") (pintype "power_in"))
      (node (ref "U1") (pin "H8") (pinfunction "VSS_H8") (pintype "power_in"))
      (node (ref "U1") (pin "H9") (pinfunction "VSS_H9") (pintype "power_in"))
      (node (ref "U1") (pin "J10") (pinfunction "VSS_J10") (pintype "power_in"))
      (node (ref "U1") (pin "J2") (pinfunction "VSS_J2") (pintype "power_in"))
      (node (ref "U1") (pin "J4") (pinfunction "VSS_J4") (pintype "power_in"))
      (node (ref "U1") (pin "J6") (pinfunction "VSS_J6") (pintype "power_in"))
      (node (ref "U1") (pin "J8") (pinfunction "VSS_J8") (pintype "power_in"))
      (node (ref "U1") (pin "K10") (pinfunction "VSS_K10") (pintype "power_in"))
      (node (ref "U1") (pin "K2") (pinfunction "VSS_K2") (pintype "power_in"))
      (node (ref "U1") (pin "K3") (pinfunction "VSS_K3") (pintype "power_in"))
      (node (ref "U1") (pin "K5") (pinfunction "VSS_K5") (pintype "power_in"))
      (node (ref "U1") (pin "K7") (pinfunction "VSS_K7") (pintype "power_in"))
      (node (ref "U1") (pin "K9") (pinfunction "VSS_K9") (pintype "power_in"))
      (node (ref "U1") (pin "L2") (pinfunction "VSS_L2") (pintype "power_in"))
      (node (ref "U2") (pin "1") (pinfunction "GND_1") (pintype "passive"))
      (node (ref "U3") (pin "1") (pinfunction "GND_1") (pintype "passive"))
      (node (ref "U4") (pin "2") (pinfunction "GND_2") (pintype "power_in"))
      (node (ref "U4") (pin "25") (pinfunction "GND_25") (pintype "power_in"))
      (node (ref "U5") (pin "1") (pinfunction "GND_1") (pintype "passive"))
      (node (ref "U6") (pin "4") (pinfunction "GND_4") (pintype "passive"))
      (node (ref "U7") (pin "1") (pinfunction "GND3_1") (pintype "passive"))
      (node (ref "U7") (pin "12") (pinfunction "GND1_12") (pintype "passive"))
      (node (ref "U7") (pin "13") (pinfunction "AGND_13") (pintype "passive"))
      (node (ref "U7") (pin "15") (pinfunction "AGND_15") (pintype "passive"))
      (node (ref "U7") (pin "17") (pinfunction "AGND_17") (pintype "passive"))
      (node (ref "U7") (pin "21") (pinfunction "PAD_21") (pintype "passive"))
      (node (ref "U7") (pin "4") (pinfunction "AGND_4") (pintype "passive"))
      (node (ref "U7") (pin "5") (pinfunction "GND2_5") (pintype "passive"))
      (node (ref "USB1") (pin "A1") (pinfunction "GND_A1") (pintype "passive"))
      (node (ref "USB1") (pin "A12") (pinfunction "GND_A12") (pintype "passive"))
      (node (ref "USB1") (pin "B1") (pinfunction "GND_B1") (pintype "passive"))
      (node (ref "USB1") (pin "B12") (pinfunction "GND_B12") (pintype "passive"))
      (node (ref "X1") (pin "2") (pinfunction "2_2") (pintype "passive"))
      (node (ref "X1") (pin "4") (pinfunction "4_4") (pintype "passive"))
    )
    (net (code "83") (name "Net-(J1-Y0)") (class "Default")
      (node (ref "J1") (pin "24") (pinfunction "Y0_24") (pintype "passive"))
      (node (ref "R1") (pin "1") (pinfunction "1_1") (pintype "passive"))
    )
    (net (code "84") (name "Net-(J1-Y1)") (class "Default")
      (node (ref "J1") (pin "23") (pinfunction "Y1_23") (pintype "passive"))
      (node (ref "R2") (pin "1") (pinfunction "1_1") (pintype "passive"))
    )
    (net (code "85") (name "Net-(LED1-A)") (class "Default")
      (node (ref "LED1") (pin "1") (pinfunction "A_1") (pintype "passive"))
      (node (ref "R13") (pin "2") (pinfunction "2_2") (pintype "passive"))
    )
    (net (code "86") (name "Net-(LED2-BULE_K)") (class "Default")
      (node (ref "LED2") (pin "3") (pinfunction "BULE_K_3") (pintype "passive"))
      (node (ref "R20") (pin "1") (pinfunction "1_1") (pintype "passive"))
    )
    (net (code "87") (name "Net-(LED2-GREEN_K)") (class "Default")
      (node (ref "LED2") (pin "2") (pinfunction "GREEN_K_2") (pintype "passive"))
      (node (ref "R19") (pin "1") (pinfunction "1_1") (pintype "passive"))
    )
    (net (code "88") (name "Net-(LED2-RED_K)") (class "Default")
      (node (ref "LED2") (pin "1") (pinfunction "RED_K_1") (pintype "passive"))
      (node (ref "R18") (pin "1") (pinfunction "1_1") (pintype "passive"))
    )
    (net (code "89") (name "Net-(P1-LEDK)") (class "Default")
      (node (ref "P1") (pin "1") (pinfunction "LEDK_1") (pintype "passive"))
      (node (ref "R16") (pin "1") (pinfunction "1_1") (pintype "passive"))
    )
    (net (code "90") (name "Net-(Q1-B)") (class "Default")
      (node (ref "Q1") (pin "1") (pinfunction "B_1") (pintype "passive"))
      (node (ref "R10") (pin "2") (pinfunction "2_2") (pintype "passive"))
    )
    (net (code "91") (name "Net-(Q2-B)") (class "Default")
      (node (ref "Q2") (pin "1") (pinfunction "B_1") (pintype "passive"))
      (node (ref "R11") (pin "2") (pinfunction "2_2") (pintype "passive"))
    )
    (net (code "92") (name "Net-(U1B-CLK)") (class "Default")
      (node (ref "U1") (pin "L3") (pinfunction "OSC_CLK_L3") (pintype "passive"))
      (node (ref "U1") (pin "M2") (pinfunction "CLK_M2") (pintype "passive"))
    )
    (net (code "93") (name "Net-(U1B-XTAL_IN)") (class "Default")
      (node (ref "C13") (pin "1") (pinfunction "1_1") (pintype "passive"))
      (node (ref "R9") (pin "1") (pinfunction "1_1") (pintype "passive"))
      (node (ref "U1") (pin "M4") (pinfunction "XTAL_IN_M4") (pintype "passive"))
      (node (ref "X1") (pin "1") (pinfunction "1_1") (pintype "passive"))
    )
    (net (code "94") (name "Net-(U1B-XTAL_OUT)") (class "Default")
      (node (ref "C10") (pin "1") (pinfunction "1_1") (pintype "passive"))
      (node (ref "R9") (pin "2") (pinfunction "2_2") (pintype "passive"))
      (node (ref "U1") (pin "M3") (pinfunction "XTAL_OUT_M3") (pintype "passive"))
      (node (ref "X1") (pin "3") (pinfunction "3_3") (pintype "passive"))
    )
    (net (code "95") (name "Net-(U1C-VDDPLL)") (class "Default")
      (node (ref "C41") (pin "1") (pinfunction "1_1") (pintype "passive"))
      (node (ref "C42") (pin "1") (pinfunction "1_1") (pintype "passive"))
      (node (ref "R25") (pin "1") (pinfunction "1_1") (pintype "passive"))
      (node (ref "U1") (pin "L4") (pinfunction "VDDPLL_L4") (pintype "power_in"))
    )
    (net (code "96") (name "Net-(U1C-VSSPLL)") (class "Default")
      (node (ref "C41") (pin "2") (pinfunction "2_2") (pintype "passive"))
      (node (ref "C42") (pin "2") (pinfunction "2_2") (pintype "passive"))
      (node (ref "R28") (pin "1") (pinfunction "1_1") (pintype "passive"))
      (node (ref "U1") (pin "K4") (pinfunction "VSSPLL_K4") (pintype "power_in"))
    )
    (net (code "97") (name "Net-(U4-VDD)") (class "Default")
      (node (ref "C6") (pin "1") (pinfunction "1_1") (pintype "passive"))
      (node (ref "R6") (pin "2") (pinfunction "2_2") (pintype "passive"))
      (node (ref "U4") (pin "5") (pinfunction "VIO_5") (pintype "passive"))
      (node (ref "U4") (pin "6") (pinfunction "VDD_6") (pintype "passive"))
    )
    (net (code "98") (name "Net-(U4-~{RS}T)") (class "Default")
      (node (ref "R6") (pin "1") (pinfunction "1_1") (pintype "passive"))
      (node (ref "U4") (pin "9") (pinfunction "~{RS}T_9") (pintype "passive"))
    )
    (net (code "99") (name "Net-(U7-FB1)") (class "Default")
      (node (ref "R21") (pin "1") (pinfunction "1_1") (pintype "passive"))
      (node (ref "R22") (pin "1") (pinfunction "1_1") (pintype "passive"))
      (node (ref "U7") (pin "14") (pinfunction "FB1_14") (pintype "passive"))
    )
    (net (code "100") (name "Net-(U7-FB2)") (class "Default")
      (node (ref "R23") (pin "1") (pinfunction "1_1") (pintype "passive"))
      (node (ref "R24") (pin "1") (pinfunction "1_1") (pintype "passive"))
      (node (ref "U7") (pin "3") (pinfunction "FB2_3") (pintype "passive"))
    )
    (net (code "101") (name "Net-(U7-FB3)") (class "Default")
      (node (ref "R26") (pin "1") (pinfunction "1_1") (pintype "passive"))
      (node (ref "R27") (pin "1") (pinfunction "1_1") (pintype "passive"))
      (node (ref "U7") (pin "2") (pinfunction "FB3_2") (pintype "passive"))
    )
    (net (code "102") (name "Net-(U7-SW1)") (class "Default")
      (node (ref "L1") (pin "1") (pinfunction "1_1") (pintype "passive"))
      (node (ref "U7") (pin "11") (pinfunction "SW1_11") (pintype "passive"))
    )
    (net (code "103") (name "Net-(U7-SW2)") (class "Default")
      (node (ref "L2") (pin "1") (pinfunction "1_1") (pintype "passive"))
      (node (ref "U7") (pin "6") (pinfunction "SW2_6") (pintype "passive"))
    )
    (net (code "104") (name "Net-(U7-SW3)") (class "Default")
      (node (ref "L3") (pin "1") (pinfunction "1_1") (pintype "passive"))
      (node (ref "U7") (pin "20") (pinfunction "SW3_20") (pintype "passive"))
    )
    (net (code "105") (name "VBUS") (class "Default")
      (node (ref "C7") (pin "2") (pinfunction "2_2") (pintype "passive"))
      (node (ref "C8") (pin "2") (pinfunction "2_2") (pintype "passive"))
      (node (ref "F1") (pin "1") (pinfunction "1_1") (pintype "passive"))
      (node (ref "J3") (pin "42") (pinfunction "42_42") (pintype "passive"))
      (node (ref "J3") (pin "44") (pinfunction "44_44") (pintype "passive"))
      (node (ref "J3") (pin "46") (pinfunction "46_46") (pintype "passive"))
      (node (ref "U4") (pin "7") (pinfunction "REGIN_7") (pintype "passive"))
      (node (ref "U4") (pin "8") (pinfunction "VBUS_8") (pintype "power_in"))
      (node (ref "USB1") (pin "A4") (pinfunction "VBUS_A4") (pintype "passive"))
      (node (ref "USB1") (pin "A9") (pinfunction "VBUS_A9") (pintype "passive"))
      (node (ref "USB1") (pin "B4") (pinfunction "VBUS_B4") (pintype "passive"))
      (node (ref "USB1") (pin "B9") (pinfunction "VBUS_B9") (pintype "passive"))
    )
    (net (code "106") (name "VCC_BANK") (class "Default")
      (node (ref "C14") (pin "2") (pinfunction "2_2") (pintype "passive"))
      (node (ref "C19") (pin "2") (pinfunction "2_2") (pintype "passive"))
      (node (ref "C5") (pin "1") (pinfunction "1_1") (pintype "passive"))
      (node (ref "J1") (pin "11") (pinfunction "DOVDD_11") (pintype "passive"))
      (node (ref "P1") (pin "11") (pinfunction "RD_11") (pintype "passive"))
      (node (ref "P1") (pin "5") (pinfunction "IOVCC_5") (pintype "passive"))
      (node (ref "R29") (pin "1") (pinfunction "1_1") (pintype "passive"))
      (node (ref "R3") (pin "2") (pinfunction "2_2") (pintype "passive"))
      (node (ref "R30") (pin "2") (pinfunction "2_2") (pintype "passive"))
      (node (ref "R5") (pin "2") (pinfunction "2_2") (pintype "passive"))
      (node (ref "U1") (pin "D3") (pinfunction "VDDIO6C_D3") (pintype "power_in"))
      (node (ref "U1") (pin "F3") (pinfunction "VDDIO7C_F3") (pintype "power_in"))
    )
    (net (code "107") (name "VIN") (class "Default")
      (node (ref "C23") (pin "1") (pinfunction "1_1") (pintype "passive"))
      (node (ref "C26") (pin "1") (pinfunction "1_1") (pintype "passive"))
      (node (ref "C27") (pin "1") (pinfunction "1_1") (pintype "passive"))
      (node (ref "F1") (pin "2") (pinfunction "2_2") (pintype "passive"))
      (node (ref "J3") (pin "48") (pinfunction "48_48") (pintype "passive"))
      (node (ref "J3") (pin "50") (pinfunction "50_50") (pintype "passive"))
      (node (ref "J3") (pin "52") (pinfunction "52_52") (pintype "passive"))
      (node (ref "P1") (pin "2") (pinfunction "LEDA_2") (pintype "passive"))
      (node (ref "R13") (pin "1") (pinfunction "1_1") (pintype "passive"))
      (node (ref "U2") (pin "3") (pinfunction "VIN_3") (pintype "passive"))
      (node (ref "U3") (pin "3") (pinfunction "VIN_3") (pintype "passive"))
      (node (ref "U7") (pin "10") (pinfunction "VIN1_10") (pintype "passive"))
      (node (ref "U7") (pin "16") (pinfunction "VCC_16") (pintype "passive"))
      (node (ref "U7") (pin "18") (pinfunction "EN3_18") (pintype "passive"))
      (node (ref "U7") (pin "19") (pinfunction "VIN3_19") (pintype "passive"))
      (node (ref "U7") (pin "7") (pinfunction "VIN2_7") (pintype "passive"))
      (node (ref "U7") (pin "8") (pinfunction "EN2_8") (pintype "passive"))
      (node (ref "U7") (pin "9") (pinfunction "EN1_9") (pintype "passive"))
    )
    (net (code "108") (name "unconnected-(J1-PadP0)") (class "Default")
      (node (ref "J1") (pin "P0") (pinfunction "P0_P0") (pintype "passive+no_connect"))
    )
    (net (code "109") (name "unconnected-(J1-STROBE-Pad1)") (class "Default")
      (node (ref "J1") (pin "1") (pinfunction "STROBE_1") (pintype "passive+no_connect"))
    )
    (net (code "110") (name "unconnected-(J2-DATA1-Pad8)") (class "Default")
      (node (ref "J2") (pin "8") (pinfunction "DATA1_8") (pintype "passive+no_connect"))
    )
    (net (code "111") (name "unconnected-(J2-DATA2-Pad1)") (class "Default")
      (node (ref "J2") (pin "1") (pinfunction "DATA2_1") (pintype "passive+no_connect"))
    )
    (net (code "112") (name "unconnected-(J3-Pad16)") (class "Default")
      (node (ref "J3") (pin "16") (pinfunction "16_16") (pintype "passive+no_connect"))
    )
    (net (code "113") (name "unconnected-(J3-Pad18)") (class "Default")
      (node (ref "J3") (pin "18") (pinfunction "18_18") (pintype "passive+no_connect"))
    )
    (net (code "114") (name "unconnected-(J3-Pad20)") (class "Default")
      (node (ref "J3") (pin "20") (pinfunction "20_20") (pintype "passive+no_connect"))
    )
    (net (code "115") (name "unconnected-(J3-Pad22)") (class "Default")
      (node (ref "J3") (pin "22") (pinfunction "22_22") (pintype "passive+no_connect"))
    )
    (net (code "116") (name "unconnected-(J3-Pad24)") (class "Default")
      (node (ref "J3") (pin "24") (pinfunction "24_24") (pintype "passive+no_connect"))
    )
    (net (code "117") (name "unconnected-(J3-Pad26)") (class "Default")
      (node (ref "J3") (pin "26") (pinfunction "26_26") (pintype "passive+no_connect"))
    )
    (net (code "118") (name "unconnected-(J3-Pad28)") (class "Default")
      (node (ref "J3") (pin "28") (pinfunction "28_28") (pintype "passive+no_connect"))
    )
    (net (code "119") (name "unconnected-(J3-Pad30)") (class "Default")
      (node (ref "J3") (pin "30") (pinfunction "30_30") (pintype "passive+no_connect"))
    )
    (net (code "120") (name "unconnected-(J3-Pad32)") (class "Default")
      (node (ref "J3") (pin "32") (pinfunction "32_32") (pintype "passive+no_connect"))
    )
    (net (code "121") (name "unconnected-(J3-Pad34)") (class "Default")
      (node (ref "J3") (pin "34") (pinfunction "34_34") (pintype "passive+no_connect"))
    )
    (net (code "122") (name "unconnected-(P1-NC-Pad6)") (class "Default")
      (node (ref "P1") (pin "6") (pinfunction "NC_6") (pintype "passive+no_connect"))
    )
    (net (code "123") (name "unconnected-(P1-PadP0)") (class "Default")
      (node (ref "P1") (pin "P0") (pinfunction "P0_P0") (pintype "passive+no_connect"))
    )
    (net (code "124") (name "unconnected-(P1-XL-Pad22)") (class "Default")
      (node (ref "P1") (pin "22") (pinfunction "XL_22") (pintype "passive"))
    )
    (net (code "125") (name "unconnected-(P1-XR-Pad24)") (class "Default")
      (node (ref "P1") (pin "24") (pinfunction "XR_24") (pintype "passive"))
    )
    (net (code "126") (name "unconnected-(P1-YD-Pad23)") (class "Default")
      (node (ref "P1") (pin "23") (pinfunction "YD_23") (pintype "passive"))
    )
    (net (code "127") (name "unconnected-(P1-YU-Pad21)") (class "Default")
      (node (ref "P1") (pin "21") (pinfunction "YU_21") (pintype "passive"))
    )
    (net (code "128") (name "unconnected-(U4-CTS-Pad18)") (class "Default")
      (node (ref "U4") (pin "18") (pinfunction "CTS_18") (pintype "passive+no_connect"))
    )
    (net (code "129") (name "unconnected-(U4-DCD-Pad24)") (class "Default")
      (node (ref "U4") (pin "24") (pinfunction "DCD_24") (pintype "passive+no_connect"))
    )
    (net (code "130") (name "unconnected-(U4-DSR-Pad22)") (class "Default")
      (node (ref "U4") (pin "22") (pinfunction "DSR_22") (pintype "passive+no_connect"))
    )
    (net (code "131") (name "unconnected-(U4-GPIO.0-Pad14)") (class "Default")
      (node (ref "U4") (pin "14") (pinfunction "GPIO.0_14") (pintype "passive+no_connect"))
    )
    (net (code "132") (name "unconnected-(U4-GPIO.1-Pad13)") (class "Default")
      (node (ref "U4") (pin "13") (pinfunction "GPIO.1_13") (pintype "passive+no_connect"))
    )
    (net (code "133") (name "unconnected-(U4-GPIO.2-Pad12)") (class "Default")
      (node (ref "U4") (pin "12") (pinfunction "GPIO.2_12") (pintype "passive+no_connect"))
    )
    (net (code "134") (name "unconnected-(U4-GPIO.3-Pad11)") (class "Default")
      (node (ref "U4") (pin "11") (pinfunction "GPIO.3_11") (pintype "passive+no_connect"))
    )
    (net (code "135") (name "unconnected-(U4-NC-Pad10)") (class "Default")
      (node (ref "U4") (pin "10") (pinfunction "NC_10") (pintype "passive+no_connect"))
    )
    (net (code "136") (name "unconnected-(U4-RI-Pad1)") (class "Default")
      (node (ref "U4") (pin "1") (pinfunction "RI_1") (pintype "passive+no_connect"))
    )
    (net (code "137") (name "unconnected-(U4-SUSPEND-Pad17)") (class "Default")
      (node (ref "U4") (pin "17") (pinfunction "SUSPEND_17") (pintype "passive+no_connect"))
    )
    (net (code "138") (name "unconnected-(U4-VPP-Pad16)") (class "Default")
      (node (ref "U4") (pin "16") (pinfunction "VPP_16") (pintype "passive+no_connect"))
    )
    (net (code "139") (name "unconnected-(U4-~{SUSPEND}-Pad15)") (class "Default")
      (node (ref "U4") (pin "15") (pinfunction "~{SUSPEND}_15") (pintype "passive+no_connect"))
    )
    (net (code "140") (name "unconnected-(USB1-CC1-PadA5)") (class "Default")
      (node (ref "USB1") (pin "A5") (pinfunction "CC1_A5") (pintype "passive"))
    )
    (net (code "141") (name "unconnected-(USB1-CC2-PadB5)") (class "Default")
      (node (ref "USB1") (pin "B5") (pinfunction "CC2_B5") (pintype "passive"))
    )
    (net (code "142") (name "unconnected-(USB1-RX1+-PadB11)") (class "Default")
      (node (ref "USB1") (pin "B11") (pinfunction "RX1+_B11") (pintype "passive"))
    )
    (net (code "143") (name "unconnected-(USB1-RX1--PadB10)") (class "Default")
      (node (ref "USB1") (pin "B10") (pinfunction "RX1-_B10") (pintype "passive"))
    )
    (net (code "144") (name "unconnected-(USB1-RX2+-PadA11)") (class "Default")
      (node (ref "USB1") (pin "A11") (pinfunction "RX2+_A11") (pintype "passive"))
    )
    (net (code "145") (name "unconnected-(USB1-RX2--PadA10)") (class "Default")
      (node (ref "USB1") (pin "A10") (pinfunction "RX2-_A10") (pintype "passive"))
    )
    (net (code "146") (name "unconnected-(USB1-SBU1-PadA8)") (class "Default")
      (node (ref "USB1") (pin "A8") (pinfunction "SBU1_A8") (pintype "passive"))
    )
    (net (code "147") (name "unconnected-(USB1-SBU2-PadB8)") (class "Default")
      (node (ref "USB1") (pin "B8") (pinfunction "SBU2_B8") (pintype "passive"))
    )
    (net (code "148") (name "unconnected-(USB1-SH1-Pad1)") (class "Default")
      (node (ref "USB1") (pin "1") (pinfunction "SH1_1") (pintype "passive"))
    )
    (net (code "149") (name "unconnected-(USB1-SH2-Pad2)") (class "Default")
      (node (ref "USB1") (pin "2") (pinfunction "SH2_2") (pintype "passive"))
    )
    (net (code "150") (name "unconnected-(USB1-SH3-Pad3)") (class "Default")
      (node (ref "USB1") (pin "3") (pinfunction "SH3_3") (pintype "passive"))
    )
    (net (code "151") (name "unconnected-(USB1-SH4-Pad4)") (class "Default")
      (node (ref "USB1") (pin "4") (pinfunction "SH4_4") (pintype "passive"))
    )
    (net (code "152") (name "unconnected-(USB1-TX1+-PadA2)") (class "Default")
      (node (ref "USB1") (pin "A2") (pinfunction "TX1+_A2") (pintype "passive"))
    )
    (net (code "153") (name "unconnected-(USB1-TX1--PadA3)") (class "Default")
      (node (ref "USB1") (pin "A3") (pinfunction "TX1-_A3") (pintype "passive"))
    )
    (net (code "154") (name "unconnected-(USB1-TX2+-PadB2)") (class "Default")
      (node (ref "USB1") (pin "B2") (pinfunction "TX2+_B2") (pintype "passive"))
    )
    (net (code "155") (name "unconnected-(USB1-TX2--PadB3)") (class "Default")
      (node (ref "USB1") (pin "B3") (pinfunction "TX2-_B3") (pintype "passive"))
    )
  )
)
